# TCA785-U.net
KiCad netlist of a schematic drawn in Altium Designer
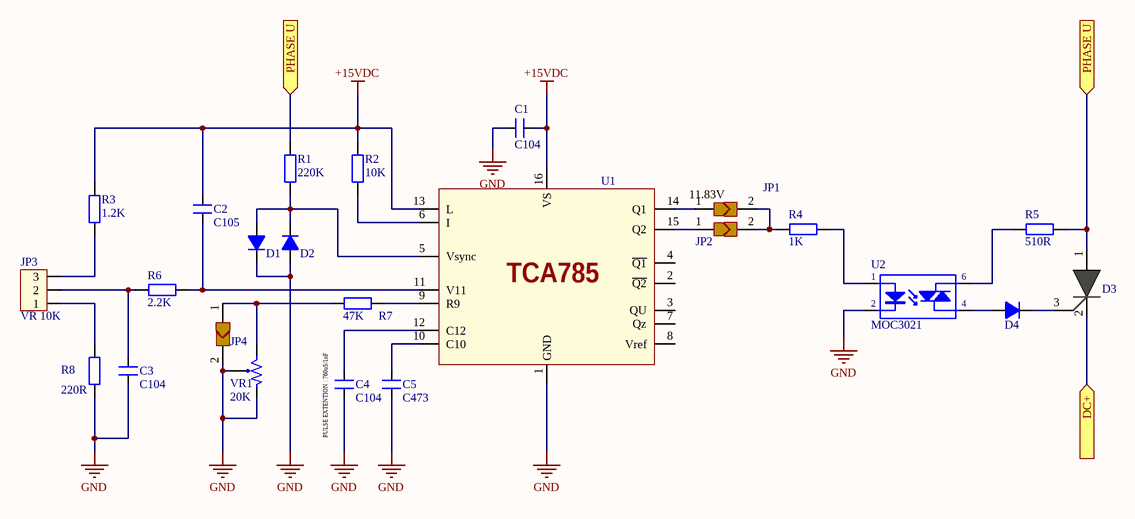
[diagram p0: TCA785-U.SchDoc]

(export (version "E")
  (design (tool "Eeschema 10.0.6"))
  (components
    (comp (ref "C1")
      (value "C104")
      (footprint "CN2-O")
      (description "CAP-gom")
      (libsource (lib "Sang_Library") (part "CAP-gom"))
    )
    (comp (ref "C2")
      (value "C105")
      (footprint "CN2-O")
      (description "CAP-gom")
      (libsource (lib "Sang_Library") (part "CAP-gom"))
    )
    (comp (ref "C3")
      (value "C104")
      (footprint "CN2-O")
      (description "CAP-gom")
      (libsource (lib "Sang_Library") (part "CAP-gom"))
    )
    (comp (ref "C4")
      (value "C104")
      (footprint "CN2-O")
      (description "CAP-gom")
      (libsource (lib "Sang_Library") (part "CAP-gom"))
    )
    (comp (ref "C5")
      (value "C473")
      (footprint "CN2-O")
      (description "CAP-gom")
      (libsource (lib "Sang_Library") (part "CAP-gom"))
    )
    (comp (ref "D1")
      (value "Diode  1N4007")
      (footprint "DO41-1A")
      (description "Diode 1A")
      (libsource (lib "Sang_Library") (part "Diode  1N4007"))
    )
    (comp (ref "D2")
      (value "Diode  1N4007")
      (footprint "DO41-1A")
      (description "Diode 1A")
      (libsource (lib "Sang_Library") (part "Diode  1N4007"))
    )
    (comp (ref "D3") (value "SCR") (footprint "TO-220") (libsource (lib "Huan") (part "BT151")))
    (comp (ref "D4")
      (value "Diode  1N4007")
      (footprint "DO41-1A")
      (description "Diode 1A")
      (libsource (lib "Sang_Library") (part "Diode  1N4007"))
    )
    (comp (ref "JP1")
      (value "PAD_Sellect")
      (footprint "PAD Select")
      (libsource (lib "Huan") (part "PAD_Sellect"))
    )
    (comp (ref "JP2")
      (value "PAD_Sellect")
      (footprint "PAD Select")
      (libsource (lib "Huan") (part "PAD_Sellect"))
    )
    (comp (ref "JP3")
      (value "VR 10K")
      (footprint "CON3")
      (description "Connector 3")
      (libsource (lib "syhaunguyen") (part "Con3"))
    )
    (comp (ref "JP4")
      (value "PAD_Sellect")
      (footprint "PAD Select")
      (libsource (lib "Huan") (part "PAD_Sellect"))
    )
    (comp (ref "R1")
      (value "220K")
      (footprint "R1/4W")
      (description "Resistor 1/4W")
      (libsource (lib "Sang_Library") (part "R1/4W"))
    )
    (comp (ref "R2")
      (value "10K")
      (footprint "R1/4W")
      (description "Resistor 1/4W")
      (libsource (lib "Sang_Library") (part "R1/4W"))
    )
    (comp (ref "R3")
      (value "1.2K")
      (footprint "R1/4W")
      (description "Resistor 1/4W")
      (libsource (lib "Sang_Library") (part "R1/4W"))
    )
    (comp (ref "R4")
      (value "1K")
      (footprint "R1/4W")
      (description "Resistor 1/4W")
      (libsource (lib "Sang_Library") (part "R1/4W"))
    )
    (comp (ref "R5")
      (value "510R")
      (footprint "R1/4W")
      (description "Resistor 1/4W")
      (libsource (lib "Sang_Library") (part "R1/4W"))
    )
    (comp (ref "R6")
      (value "2.2K")
      (footprint "R1/4W")
      (description "Resistor 1/4W")
      (libsource (lib "Sang_Library") (part "R1/4W"))
    )
    (comp (ref "R7")
      (value "47K")
      (footprint "R1/4W")
      (description "Resistor 1/4W")
      (libsource (lib "Sang_Library") (part "R1/4W"))
    )
    (comp (ref "R8")
      (value "220R")
      (footprint "R1/4W")
      (description "Resistor 1/4W")
      (libsource (lib "Sang_Library") (part "R1/4W"))
    )
    (comp (ref "U1") (value "TCA785Q") (footprint "DIP-16") (libsource (lib "Huan") (part "TCA785Q")))
    (comp (ref "U2")
      (value "MOC3021")
      (footprint "DIP6/W0.3 - MOC3021")
      (description "Single Opto")
      (libsource (lib "Sang_Library") (part "MOC3021"))
    )
    (comp (ref "VR1")
      (value "20K")
      (footprint "VR")
      (description "Var Resistor RM065")
      (libsource (lib "Sang_Library") (part "VR"))
    )
  )
  (nets
    (net (code "1") (name "+15VDC") (class "Default")
      (node (ref "C1") (pin "2") (pinfunction "2_2") (pintype "passive"))
      (node (ref "C2") (pin "2") (pinfunction "2_2") (pintype "passive"))
      (node (ref "R2") (pin "1") (pinfunction "1_1") (pintype "passive"))
      (node (ref "R3") (pin "2") (pinfunction "2_2") (pintype "passive"))
      (node (ref "U1") (pin "13") (pinfunction "L_13") (pintype "passive"))
      (node (ref "U1") (pin "16") (pinfunction "VS_16") (pintype "passive"))
    )
    (net (code "2") (name "/DC+") (class "Default")
      (node (ref "D3") (pin "2") (pinfunction "K_2") (pintype "passive"))
    )
    (net (code "3") (name "/PHASE U") (class "Default")
      (node (ref "D3") (pin "1") (pinfunction "A_1") (pintype "passive"))
      (node (ref "R1") (pin "1") (pinfunction "1_1") (pintype "passive"))
      (node (ref "R5") (pin "1") (pinfunction "1_1") (pintype "passive"))
    )
    (net (code "4") (name "GND") (class "Default")
      (node (ref "C1") (pin "1") (pinfunction "1_1") (pintype "passive"))
      (node (ref "C3") (pin "1") (pinfunction "1_1") (pintype "passive"))
      (node (ref "C4") (pin "1") (pinfunction "1_1") (pintype "passive"))
      (node (ref "C5") (pin "1") (pinfunction "1_1") (pintype "passive"))
      (node (ref "D1") (pin "2") (pinfunction "2_2") (pintype "passive"))
      (node (ref "D2") (pin "1") (pinfunction "1_1") (pintype "passive"))
      (node (ref "JP4") (pin "2") (pinfunction "2_2") (pintype "passive"))
      (node (ref "R8") (pin "1") (pinfunction "1_1") (pintype "passive"))
      (node (ref "U1") (pin "1") (pinfunction "GND_1") (pintype "passive"))
      (node (ref "U2") (pin "2") (pinfunction "K_2") (pintype "passive"))
      (node (ref "VR1") (pin "1") (pinfunction "1_1") (pintype "passive"))
      (node (ref "VR1") (pin "2") (pinfunction "2_2") (pintype "passive"))
    )
    (net (code "5") (name "Net-(C3-Pad2)") (class "Default")
      (node (ref "C3") (pin "2") (pinfunction "2_2") (pintype "passive"))
      (node (ref "JP3") (pin "2") (pinfunction "2_2") (pintype "passive"))
      (node (ref "R6") (pin "2") (pinfunction "2_2") (pintype "passive"))
    )
    (net (code "6") (name "Net-(D3-G)") (class "Default")
      (node (ref "D3") (pin "3") (pinfunction "G_3") (pintype "passive"))
      (node (ref "D4") (pin "2") (pinfunction "2_2") (pintype "passive"))
    )
    (net (code "7") (name "Net-(JP1-Pad2)") (class "Default")
      (node (ref "JP1") (pin "2") (pinfunction "2_2") (pintype "passive"))
      (node (ref "JP2") (pin "2") (pinfunction "2_2") (pintype "passive"))
      (node (ref "R4") (pin "2") (pinfunction "2_2") (pintype "passive"))
    )
    (net (code "8") (name "Net-(JP3-Pad1)") (class "Default")
      (node (ref "JP3") (pin "1") (pinfunction "1_1") (pintype "passive"))
      (node (ref "R8") (pin "2") (pinfunction "2_2") (pintype "passive"))
    )
    (net (code "9") (name "Net-(JP3-Pad3)") (class "Default")
      (node (ref "JP3") (pin "3") (pinfunction "3_3") (pintype "passive"))
      (node (ref "R3") (pin "1") (pinfunction "1_1") (pintype "passive"))
    )
    (net (code "10") (name "Net-(JP4-Pad1)") (class "Default")
      (node (ref "JP4") (pin "1") (pinfunction "1_1") (pintype "passive"))
      (node (ref "R7") (pin "1") (pinfunction "1_1") (pintype "passive"))
      (node (ref "VR1") (pin "3") (pinfunction "3_3") (pintype "passive"))
    )
    (net (code "11") (name "Net-(U1-C10)") (class "Default")
      (node (ref "C5") (pin "2") (pinfunction "2_2") (pintype "passive"))
      (node (ref "U1") (pin "10") (pinfunction "C10_10") (pintype "passive"))
    )
    (net (code "12") (name "Net-(U1-C12)") (class "Default")
      (node (ref "C4") (pin "2") (pinfunction "2_2") (pintype "passive"))
      (node (ref "U1") (pin "12") (pinfunction "C12_12") (pintype "passive"))
    )
    (net (code "13") (name "Net-(U1-I)") (class "Default")
      (node (ref "R2") (pin "2") (pinfunction "2_2") (pintype "passive"))
      (node (ref "U1") (pin "6") (pinfunction "I_6") (pintype "passive"))
    )
    (net (code "14") (name "Net-(U1-Q1)") (class "Default")
      (node (ref "JP1") (pin "1") (pinfunction "1_1") (pintype "passive"))
      (node (ref "U1") (pin "14") (pinfunction "Q1_14") (pintype "passive"))
    )
    (net (code "15") (name "Net-(U1-Q2)") (class "Default")
      (node (ref "JP2") (pin "1") (pinfunction "1_1") (pintype "passive"))
      (node (ref "U1") (pin "15") (pinfunction "Q2_15") (pintype "passive"))
    )
    (net (code "16") (name "Net-(U1-R9)") (class "Default")
      (node (ref "R7") (pin "2") (pinfunction "2_2") (pintype "passive"))
      (node (ref "U1") (pin "9") (pinfunction "R9_9") (pintype "passive"))
    )
    (net (code "17") (name "Net-(U1-V11)") (class "Default")
      (node (ref "C2") (pin "1") (pinfunction "1_1") (pintype "passive"))
      (node (ref "R6") (pin "1") (pinfunction "1_1") (pintype "passive"))
      (node (ref "U1") (pin "11") (pinfunction "V11_11") (pintype "passive"))
    )
    (net (code "18") (name "Net-(U1-Vsync)") (class "Default")
      (node (ref "D1") (pin "1") (pinfunction "1_1") (pintype "passive"))
      (node (ref "D2") (pin "2") (pinfunction "2_2") (pintype "passive"))
      (node (ref "R1") (pin "2") (pinfunction "2_2") (pintype "passive"))
      (node (ref "U1") (pin "5") (pinfunction "Vsync_5") (pintype "passive"))
    )
    (net (code "19") (name "Net-(U2-A)") (class "Default")
      (node (ref "R4") (pin "1") (pinfunction "1_1") (pintype "passive"))
      (node (ref "U2") (pin "1") (pinfunction "A_1") (pintype "passive"))
    )
    (net (code "20") (name "Net-(U2-C)") (class "Default")
      (node (ref "R5") (pin "2") (pinfunction "2_2") (pintype "passive"))
      (node (ref "U2") (pin "6") (pinfunction "C_6") (pintype "passive"))
    )
    (net (code "21") (name "Net-(U2-E)") (class "Default")
      (node (ref "D4") (pin "1") (pinfunction "1_1") (pintype "passive"))
      (node (ref "U2") (pin "4") (pinfunction "E_4") (pintype "passive"))
    )
    (net (code "22") (name "unconnected-(U1-QU-Pad3)") (class "Default")
      (node (ref "U1") (pin "3") (pinfunction "QU_3") (pintype "passive"))
    )
    (net (code "23") (name "unconnected-(U1-Qz-Pad7)") (class "Default")
      (node (ref "U1") (pin "7") (pinfunction "Qz_7") (pintype "passive"))
    )
    (net (code "24") (name "unconnected-(U1-Vref-Pad8)") (class "Default")
      (node (ref "U1") (pin "8") (pinfunction "Vref_8") (pintype "passive"))
    )
    (net (code "25") (name "unconnected-(U1-~{Q1}-Pad4)") (class "Default")
      (node (ref "U1") (pin "4") (pinfunction "~{Q1}_4") (pintype "passive"))
    )
    (net (code "26") (name "unconnected-(U1-~{Q2}-Pad2)") (class "Default")
      (node (ref "U1") (pin "2") (pinfunction "~{Q2}_2") (pintype "passive"))
    )
  )
)
